# 01_Power.net
KiCad netlist of a schematic drawn in Altium Designer
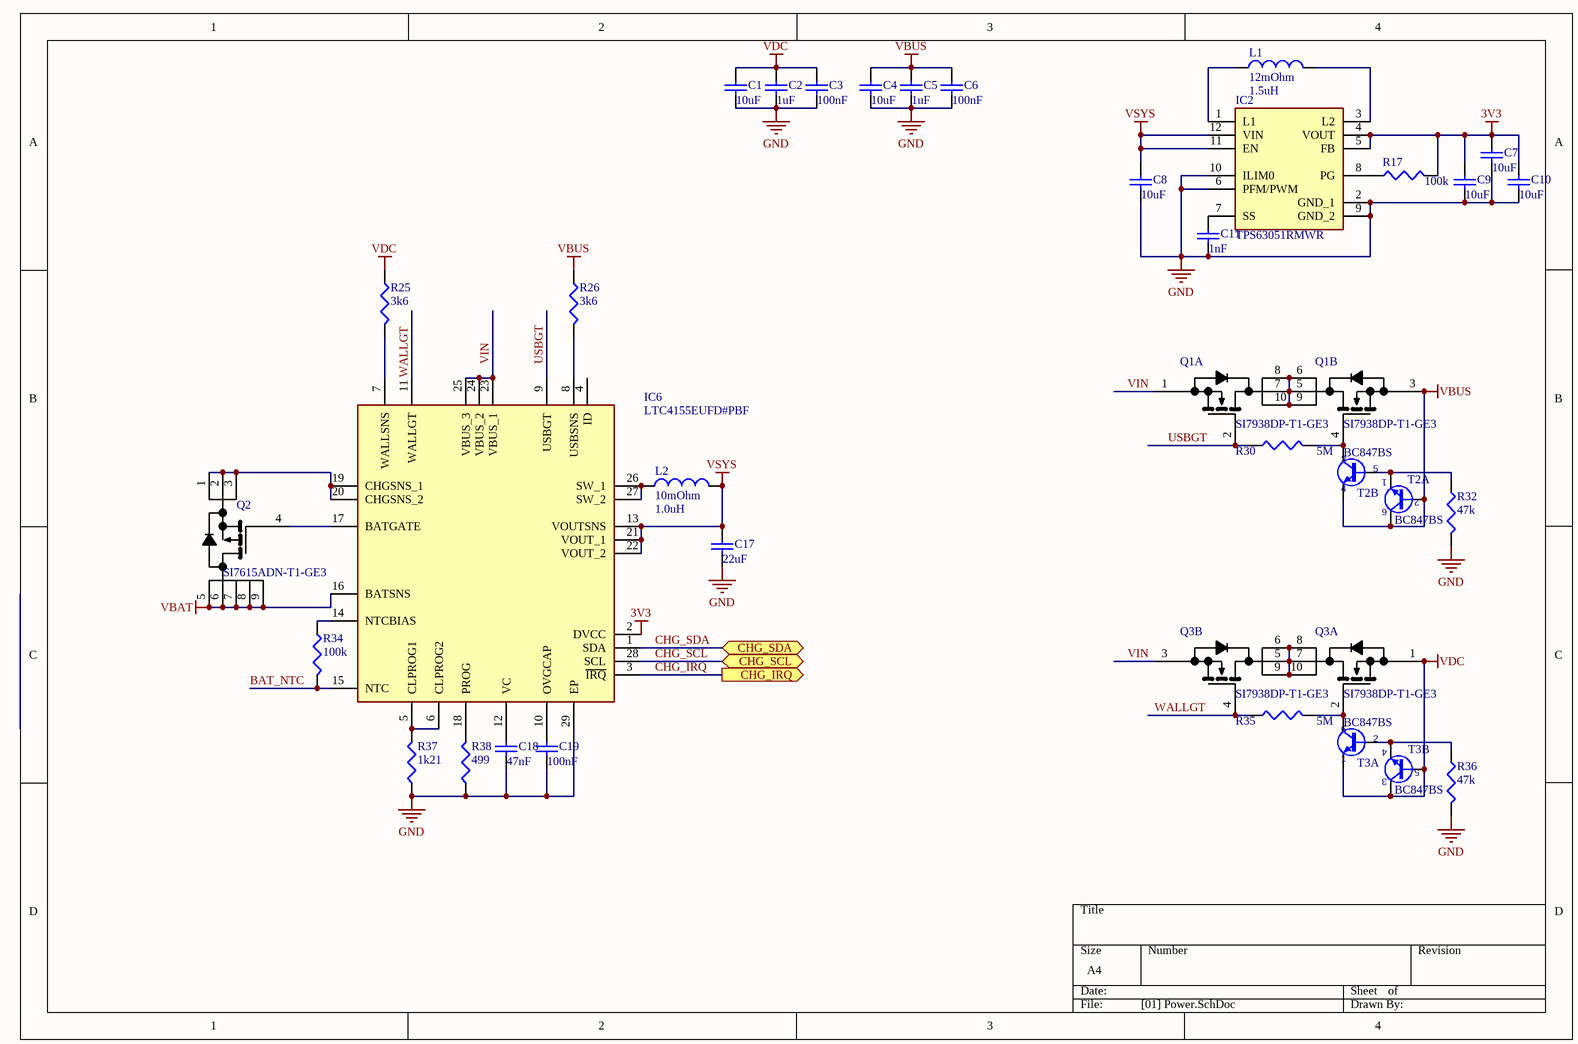
[diagram p0: [01] Power.SchDoc]

(export (version "E")
  (design (tool "Eeschema 10.0.6"))
  (components
    (comp (ref "C1")
      (value "10uF")
      (footprint "1608[0603]")
      (description "Capacitor (Semiconductor SIM Model)")
      (fields (field (name "Comment") "Cap Semi") (field (name "PUBLISHER") "Altium Limited"))
      (libsource (lib "Miscellaneous Devices") (part "Cap Semi"))
    )
    (comp (ref "C2")
      (value "1uF")
      (footprint "1608[0603]")
      (description "Capacitor (Semiconductor SIM Model)")
      (fields (field (name "Comment") "Cap Semi") (field (name "PUBLISHER") "Altium Limited"))
      (libsource (lib "Miscellaneous Devices") (part "Cap Semi"))
    )
    (comp (ref "C3")
      (value "100nF")
      (footprint "1608[0603]")
      (description "Capacitor (Semiconductor SIM Model)")
      (fields (field (name "Comment") "Cap Semi") (field (name "PUBLISHER") "Altium Limited"))
      (libsource (lib "Miscellaneous Devices") (part "Cap Semi"))
    )
    (comp (ref "C4")
      (value "10uF")
      (footprint "1608[0603]")
      (description "Capacitor (Semiconductor SIM Model)")
      (fields (field (name "Comment") "Cap Semi") (field (name "PUBLISHER") "Altium Limited"))
      (libsource (lib "Miscellaneous Devices") (part "Cap Semi"))
    )
    (comp (ref "C5")
      (value "1uF")
      (footprint "1608[0603]")
      (description "Capacitor (Semiconductor SIM Model)")
      (fields (field (name "Comment") "Cap Semi") (field (name "PUBLISHER") "Altium Limited"))
      (libsource (lib "Miscellaneous Devices") (part "Cap Semi"))
    )
    (comp (ref "C6")
      (value "100nF")
      (footprint "1608[0603]")
      (description "Capacitor (Semiconductor SIM Model)")
      (fields (field (name "Comment") "Cap Semi") (field (name "PUBLISHER") "Altium Limited"))
      (libsource (lib "Miscellaneous Devices") (part "Cap Semi"))
    )
    (comp (ref "C7")
      (value "10uF")
      (footprint "1608[0603]")
      (description "Capacitor (Semiconductor SIM Model)")
      (fields (field (name "Comment") "Cap Semi") (field (name "PUBLISHER") "Altium Limited"))
      (libsource (lib "Miscellaneous Devices") (part "Cap Semi"))
    )
    (comp (ref "C8")
      (value "10uF")
      (footprint "1608[0603]")
      (description "Capacitor (Semiconductor SIM Model)")
      (fields (field (name "Comment") "Cap Semi") (field (name "PUBLISHER") "Altium Limited"))
      (libsource (lib "Miscellaneous Devices") (part "Cap Semi"))
    )
    (comp (ref "C9")
      (value "10uF")
      (footprint "1608[0603]")
      (description "Capacitor (Semiconductor SIM Model)")
      (fields (field (name "Comment") "Cap Semi") (field (name "PUBLISHER") "Altium Limited"))
      (libsource (lib "Miscellaneous Devices") (part "Cap Semi"))
    )
    (comp (ref "C10")
      (value "10uF")
      (footprint "1608[0603]")
      (description "Capacitor (Semiconductor SIM Model)")
      (fields (field (name "Comment") "Cap Semi") (field (name "PUBLISHER") "Altium Limited"))
      (libsource (lib "Miscellaneous Devices") (part "Cap Semi"))
    )
    (comp (ref "C11")
      (value "1nF")
      (footprint "1608[0603]")
      (description "Capacitor (Semiconductor SIM Model)")
      (fields (field (name "Comment") "Cap Semi") (field (name "PUBLISHER") "Altium Limited"))
      (libsource (lib "Miscellaneous Devices") (part "Cap Semi"))
    )
    (comp (ref "C17")
      (value "22uF")
      (footprint "1608[0603]")
      (description "Capacitor (Semiconductor SIM Model)")
      (fields (field (name "Comment") "Cap Semi") (field (name "PUBLISHER") "Altium Limited"))
      (libsource (lib "Miscellaneous Devices") (part "Cap Semi"))
    )
    (comp (ref "C18")
      (value "47nF")
      (footprint "1608[0603]")
      (description "Capacitor (Semiconductor SIM Model)")
      (fields (field (name "Comment") "Cap Semi") (field (name "PUBLISHER") "Altium Limited"))
      (libsource (lib "Miscellaneous Devices") (part "Cap Semi"))
    )
    (comp (ref "C19")
      (value "100nF")
      (footprint "1608[0603]")
      (description "Capacitor (Semiconductor SIM Model)")
      (fields (field (name "Comment") "Cap Semi") (field (name "PUBLISHER") "Altium Limited"))
      (libsource (lib "Miscellaneous Devices") (part "Cap Semi"))
    )
    (comp (ref "IC2")
      (value "TPS63051RMWR")
      (footprint "SamacSys:QFN50P250X250X100-12N-D")
      (description "Integrated Circuit")
      (libsource (lib "SamacSys") (part "TPS63051RMWR"))
    )
    (comp (ref "IC6")
      (value "LTC4155EUFD#PBF")
      (footprint "SamacSys:QFN50P400X500X80-29N-D")
      (description "Integrated Circuit")
      (libsource (lib "SamacSys") (part "LTC4155EUFD#PBF"))
    )
    (comp (ref "L1")
      (value "12mOhm")
      (footprint "INDP2523X23N")
      (description "Inductor SRN6045TA-1R5Y")
      (fields (field (name "ALTIUM_VALUE") "1.5uH") (field (name "PUBLISHER") "Altium Limited"))
      (libsource (lib "Miscellaneous Devices") (part "Inductor"))
    )
    (comp (ref "L2")
      (value "10mOhm")
      (footprint "INDP2523X23N")
      (description "Inductor SRN6045TA-1R0Y")
      (fields (field (name "ALTIUM_VALUE") "1.0uH") (field (name "PUBLISHER") "Altium Limited"))
      (libsource (lib "Miscellaneous Devices") (part "Inductor"))
    )
    (comp (ref "Q1")
      (value "SI7938DP-T1-GE3")
      (footprint "SamacSys:POWERPAK-SO8_1")
      (description "MOSFET (N-Channel)")
      (libsource (lib "SamacSys") (part "SI7938DP-T1-GE3"))
    )
    (comp (ref "Q2")
      (value "SI7615ADN-T1-GE3")
      (footprint "SamacSys:PowerPAK1212-8 Single")
      (description "MOSFET (P-Channel)")
      (fields (field (name "MANUFACTURER_PART_NUMBER") "SIS413DN-T1-GE3"))
      (libsource (lib "SamacSys") (part "SI7615ADN-T1-GE3"))
    )
    (comp (ref "Q3")
      (value "SI7938DP-T1-GE3")
      (footprint "SamacSys:POWERPAK-SO8_1")
      (description "MOSFET (N-Channel)")
      (libsource (lib "SamacSys") (part "SI7938DP-T1-GE3"))
    )
    (comp (ref "R17")
      (value "100k")
      (footprint "J1-0603")
      (description "Resistor")
      (fields (field (name "Comment") "Res3") (field (name "PUBLISHER") "Altium Limited"))
      (libsource (lib "Miscellaneous Devices") (part "Res3"))
    )
    (comp (ref "R25")
      (value "3k6")
      (footprint "J1-0603")
      (description "Resistor")
      (fields (field (name "Comment") "Res3") (field (name "PUBLISHER") "Altium Limited"))
      (libsource (lib "Miscellaneous Devices") (part "Res3"))
    )
    (comp (ref "R26")
      (value "3k6")
      (footprint "J1-0603")
      (description "Resistor")
      (fields (field (name "Comment") "Res3") (field (name "PUBLISHER") "Altium Limited"))
      (libsource (lib "Miscellaneous Devices") (part "Res3"))
    )
    (comp (ref "R30")
      (value "5M")
      (footprint "J1-0603")
      (description "Resistor")
      (fields (field (name "Comment") "Res3") (field (name "PUBLISHER") "Altium Limited"))
      (libsource (lib "Miscellaneous Devices") (part "Res3"))
    )
    (comp (ref "R32")
      (value "47k")
      (footprint "J1-0603")
      (description "Resistor")
      (fields (field (name "Comment") "Res3") (field (name "PUBLISHER") "Altium Limited"))
      (libsource (lib "Miscellaneous Devices") (part "Res3"))
    )
    (comp (ref "R34")
      (value "100k")
      (footprint "J1-0603")
      (description "Resistor")
      (fields (field (name "Comment") "Res3") (field (name "PUBLISHER") "Altium Limited"))
      (libsource (lib "Miscellaneous Devices") (part "Res3"))
    )
    (comp (ref "R35")
      (value "5M")
      (footprint "J1-0603")
      (description "Resistor")
      (fields (field (name "Comment") "Res3") (field (name "PUBLISHER") "Altium Limited"))
      (libsource (lib "Miscellaneous Devices") (part "Res3"))
    )
    (comp (ref "R36")
      (value "47k")
      (footprint "J1-0603")
      (description "Resistor")
      (fields (field (name "Comment") "Res3") (field (name "PUBLISHER") "Altium Limited"))
      (libsource (lib "Miscellaneous Devices") (part "Res3"))
    )
    (comp (ref "R37")
      (value "1k21")
      (footprint "J1-0603")
      (description "Resistor")
      (fields (field (name "Comment") "Res3") (field (name "PUBLISHER") "Altium Limited"))
      (libsource (lib "Miscellaneous Devices") (part "Res3"))
    )
    (comp (ref "R38")
      (value "499")
      (footprint "J1-0603")
      (description "Resistor")
      (fields (field (name "Comment") "Res3") (field (name "PUBLISHER") "Altium Limited"))
      (libsource (lib "Miscellaneous Devices") (part "Res3"))
    )
    (comp (ref "T2")
      (value "BC847BS")
      (footprint "SOT65P210X110-6N")
      (description "45V 100mA Dual NPN General-Purpose Transistor")
      (fields (field (name "MANUFACTURER") "NXP SEMICONDUCTORS") (field (name "AUTHOR") "CERN DEM JMW"))
      (libsource (lib "") (part "BC847BS_1"))
    )
    (comp (ref "T3")
      (value "BC847BS")
      (footprint "SOT65P210X110-6N")
      (description "45V 100mA Dual NPN General-Purpose Transistor")
      (fields (field (name "MANUFACTURER") "NXP SEMICONDUCTORS") (field (name "AUTHOR") "CERN DEM JMW"))
      (libsource (lib "ICs And Semiconductors") (part "BC847BS"))
    )
  )
  (nets
    (net (code "1") (name "/BAT_NTC") (class "Default")
      (node (ref "IC6") (pin "15") (pinfunction "NTC_15") (pintype "passive"))
      (node (ref "R34") (pin "2") (pinfunction "2_2") (pintype "passive"))
    )
    (net (code "2") (name "/CHG_IRQ") (class "Default")
      (node (ref "IC6") (pin "3") (pinfunction "~{IRQ}_3") (pintype "passive"))
    )
    (net (code "3") (name "/CHG_SCL") (class "Default")
      (node (ref "IC6") (pin "28") (pinfunction "SCL_28") (pintype "passive"))
    )
    (net (code "4") (name "/CHG_SDA") (class "Default")
      (node (ref "IC6") (pin "1") (pinfunction "SDA_1") (pintype "passive"))
    )
    (net (code "5") (name "/USBGT") (class "Default")
      (node (ref "IC6") (pin "9") (pinfunction "USBGT_9") (pintype "passive"))
      (node (ref "Q1") (pin "2") (pinfunction "G1_2") (pintype "passive"))
      (node (ref "R30") (pin "1") (pinfunction "1_1") (pintype "passive"))
    )
    (net (code "6") (name "/VIN") (class "Default")
      (node (ref "IC6") (pin "23") (pinfunction "VBUS_1_23") (pintype "passive"))
      (node (ref "IC6") (pin "24") (pinfunction "VBUS_2_24") (pintype "passive"))
      (node (ref "IC6") (pin "25") (pinfunction "VBUS_3_25") (pintype "passive"))
      (node (ref "Q1") (pin "1") (pinfunction "S1_1") (pintype "passive"))
      (node (ref "Q3") (pin "3") (pinfunction "S2_3") (pintype "passive"))
    )
    (net (code "7") (name "/WALLGT") (class "Default")
      (node (ref "IC6") (pin "11") (pinfunction "WALLGT_11") (pintype "passive"))
      (node (ref "Q3") (pin "4") (pinfunction "G2_4") (pintype "passive"))
      (node (ref "R35") (pin "1") (pinfunction "1_1") (pintype "passive"))
    )
    (net (code "8") (name "3V3") (class "Default")
      (node (ref "C10") (pin "2") (pinfunction "2_2") (pintype "passive"))
      (node (ref "C7") (pin "2") (pinfunction "2_2") (pintype "passive"))
      (node (ref "C9") (pin "2") (pinfunction "2_2") (pintype "passive"))
      (node (ref "IC2") (pin "4") (pinfunction "VOUT_4") (pintype "passive"))
      (node (ref "IC2") (pin "5") (pinfunction "FB_5") (pintype "passive"))
      (node (ref "IC6") (pin "2") (pinfunction "DVCC_2") (pintype "passive"))
      (node (ref "R17") (pin "2") (pinfunction "2_2") (pintype "passive"))
    )
    (net (code "9") (name "GND") (class "Default")
      (node (ref "C1") (pin "1") (pinfunction "1_1") (pintype "passive"))
      (node (ref "C10") (pin "1") (pinfunction "1_1") (pintype "passive"))
      (node (ref "C11") (pin "1") (pinfunction "1_1") (pintype "passive"))
      (node (ref "C17") (pin "1") (pinfunction "1_1") (pintype "passive"))
      (node (ref "C18") (pin "1") (pinfunction "1_1") (pintype "passive"))
      (node (ref "C19") (pin "1") (pinfunction "1_1") (pintype "passive"))
      (node (ref "C2") (pin "1") (pinfunction "1_1") (pintype "passive"))
      (node (ref "C3") (pin "1") (pinfunction "1_1") (pintype "passive"))
      (node (ref "C4") (pin "1") (pinfunction "1_1") (pintype "passive"))
      (node (ref "C5") (pin "1") (pinfunction "1_1") (pintype "passive"))
      (node (ref "C6") (pin "1") (pinfunction "1_1") (pintype "passive"))
      (node (ref "C7") (pin "1") (pinfunction "1_1") (pintype "passive"))
      (node (ref "C8") (pin "1") (pinfunction "1_1") (pintype "passive"))
      (node (ref "C9") (pin "1") (pinfunction "1_1") (pintype "passive"))
      (node (ref "IC2") (pin "10") (pinfunction "ILIM0_10") (pintype "passive"))
      (node (ref "IC2") (pin "2") (pinfunction "GND_1_2") (pintype "passive"))
      (node (ref "IC2") (pin "6") (pinfunction "PFM/PWM_6") (pintype "passive"))
      (node (ref "IC2") (pin "9") (pinfunction "GND_2_9") (pintype "passive"))
      (node (ref "IC6") (pin "29") (pinfunction "EP_29") (pintype "passive"))
      (node (ref "R32") (pin "2") (pinfunction "2_2") (pintype "passive"))
      (node (ref "R36") (pin "2") (pinfunction "2_2") (pintype "passive"))
      (node (ref "R37") (pin "1") (pinfunction "1_1") (pintype "passive"))
      (node (ref "R38") (pin "1") (pinfunction "1_1") (pintype "passive"))
    )
    (net (code "10") (name "Net-(IC2-L1)") (class "Default")
      (node (ref "IC2") (pin "1") (pinfunction "L1_1") (pintype "passive"))
      (node (ref "L1") (pin "1") (pinfunction "1_1") (pintype "passive"))
    )
    (net (code "11") (name "Net-(IC2-L2)") (class "Default")
      (node (ref "IC2") (pin "3") (pinfunction "L2_3") (pintype "passive"))
      (node (ref "L1") (pin "2") (pinfunction "2_2") (pintype "passive"))
    )
    (net (code "12") (name "Net-(IC2-PG)") (class "Default")
      (node (ref "IC2") (pin "8") (pinfunction "PG_8") (pintype "passive"))
      (node (ref "R17") (pin "1") (pinfunction "1_1") (pintype "passive"))
    )
    (net (code "13") (name "Net-(IC2-SS)") (class "Default")
      (node (ref "C11") (pin "2") (pinfunction "2_2") (pintype "passive"))
      (node (ref "IC2") (pin "7") (pinfunction "SS_7") (pintype "passive"))
    )
    (net (code "14") (name "Net-(IC6-BATGATE)") (class "Default")
      (node (ref "IC6") (pin "17") (pinfunction "BATGATE_17") (pintype "passive"))
      (node (ref "Q2") (pin "4") (pinfunction "G_4") (pintype "passive"))
    )
    (net (code "15") (name "Net-(IC6-CHGSNS_1)") (class "Default")
      (node (ref "IC6") (pin "19") (pinfunction "CHGSNS_1_19") (pintype "passive"))
      (node (ref "IC6") (pin "20") (pinfunction "CHGSNS_2_20") (pintype "passive"))
      (node (ref "Q2") (pin "1") (pinfunction "S_1") (pintype "passive"))
      (node (ref "Q2") (pin "2") (pinfunction "S_2") (pintype "passive"))
      (node (ref "Q2") (pin "3") (pinfunction "S_3") (pintype "passive"))
    )
    (net (code "16") (name "Net-(IC6-CLPROG1)") (class "Default")
      (node (ref "IC6") (pin "5") (pinfunction "CLPROG1_5") (pintype "passive"))
      (node (ref "IC6") (pin "6") (pinfunction "CLPROG2_6") (pintype "passive"))
      (node (ref "R37") (pin "2") (pinfunction "2_2") (pintype "passive"))
    )
    (net (code "17") (name "Net-(IC6-NTCBIAS)") (class "Default")
      (node (ref "IC6") (pin "14") (pinfunction "NTCBIAS_14") (pintype "passive"))
      (node (ref "R34") (pin "1") (pinfunction "1_1") (pintype "passive"))
    )
    (net (code "18") (name "Net-(IC6-OVGCAP)") (class "Default")
      (node (ref "C19") (pin "2") (pinfunction "2_2") (pintype "passive"))
      (node (ref "IC6") (pin "10") (pinfunction "OVGCAP_10") (pintype "passive"))
    )
    (net (code "19") (name "Net-(IC6-PROG)") (class "Default")
      (node (ref "IC6") (pin "18") (pinfunction "PROG_18") (pintype "passive"))
      (node (ref "R38") (pin "2") (pinfunction "2_2") (pintype "passive"))
    )
    (net (code "20") (name "Net-(IC6-SW_1)") (class "Default")
      (node (ref "IC6") (pin "26") (pinfunction "SW_1_26") (pintype "passive"))
      (node (ref "IC6") (pin "27") (pinfunction "SW_2_27") (pintype "passive"))
      (node (ref "L2") (pin "1") (pinfunction "1_1") (pintype "passive"))
    )
    (net (code "21") (name "Net-(IC6-USBSNS)") (class "Default")
      (node (ref "IC6") (pin "8") (pinfunction "USBSNS_8") (pintype "passive"))
      (node (ref "R26") (pin "2") (pinfunction "2_2") (pintype "passive"))
    )
    (net (code "22") (name "Net-(IC6-VC)") (class "Default")
      (node (ref "C18") (pin "2") (pinfunction "2_2") (pintype "passive"))
      (node (ref "IC6") (pin "12") (pinfunction "VC_12") (pintype "passive"))
    )
    (net (code "23") (name "Net-(IC6-WALLSNS)") (class "Default")
      (node (ref "IC6") (pin "7") (pinfunction "WALLSNS_7") (pintype "passive"))
      (node (ref "R25") (pin "2") (pinfunction "2_2") (pintype "passive"))
    )
    (net (code "24") (name "Net-(Q1A-D1_1)") (class "Default")
      (node (ref "Q1") (pin "10") (pinfunction "D1_3_10") (pintype "passive"))
      (node (ref "Q1") (pin "5") (pinfunction "D2_1_5") (pintype "passive"))
      (node (ref "Q1") (pin "6") (pinfunction "D2_2_6") (pintype "passive"))
      (node (ref "Q1") (pin "7") (pinfunction "D1_1_7") (pintype "passive"))
      (node (ref "Q1") (pin "8") (pinfunction "D1_2_8") (pintype "passive"))
      (node (ref "Q1") (pin "9") (pinfunction "D2_3_9") (pintype "passive"))
    )
    (net (code "25") (name "Net-(Q1B-G2)") (class "Default")
      (node (ref "Q1") (pin "4") (pinfunction "G2_4") (pintype "passive"))
      (node (ref "R30") (pin "2") (pinfunction "2_2") (pintype "passive"))
      (node (ref "T2") (pin "3") (pinfunction "C_3") (pintype "passive"))
    )
    (net (code "26") (name "Net-(Q3A-D1_1)") (class "Default")
      (node (ref "Q3") (pin "10") (pinfunction "D1_3_10") (pintype "passive"))
      (node (ref "Q3") (pin "5") (pinfunction "D2_1_5") (pintype "passive"))
      (node (ref "Q3") (pin "6") (pinfunction "D2_2_6") (pintype "passive"))
      (node (ref "Q3") (pin "7") (pinfunction "D1_1_7") (pintype "passive"))
      (node (ref "Q3") (pin "8") (pinfunction "D1_2_8") (pintype "passive"))
      (node (ref "Q3") (pin "9") (pinfunction "D2_3_9") (pintype "passive"))
    )
    (net (code "27") (name "Net-(Q3A-G1)") (class "Default")
      (node (ref "Q3") (pin "2") (pinfunction "G1_2") (pintype "passive"))
      (node (ref "R35") (pin "2") (pinfunction "2_2") (pintype "passive"))
      (node (ref "T3") (pin "6") (pinfunction "C_6") (pintype "passive"))
    )
    (net (code "28") (name "Net-(T2A-E)") (class "Default")
      (node (ref "R32") (pin "1") (pinfunction "1_1") (pintype "passive"))
      (node (ref "T2") (pin "1") (pinfunction "E_1") (pintype "passive"))
      (node (ref "T2") (pin "5") (pinfunction "B_5") (pintype "passive"))
    )
    (net (code "29") (name "Net-(T3A-B)") (class "Default")
      (node (ref "R36") (pin "1") (pinfunction "1_1") (pintype "passive"))
      (node (ref "T3") (pin "2") (pinfunction "B_2") (pintype "passive"))
      (node (ref "T3") (pin "4") (pinfunction "E_4") (pintype "passive"))
    )
    (net (code "30") (name "VBAT") (class "Default")
      (node (ref "IC6") (pin "16") (pinfunction "BATSNS_16") (pintype "passive"))
      (node (ref "Q2") (pin "5") (pinfunction "D_5") (pintype "passive"))
      (node (ref "Q2") (pin "6") (pinfunction "D_6") (pintype "passive"))
      (node (ref "Q2") (pin "7") (pinfunction "D_7") (pintype "passive"))
      (node (ref "Q2") (pin "8") (pinfunction "D_8") (pintype "passive"))
      (node (ref "Q2") (pin "9") (pinfunction "D_9") (pintype "passive"))
    )
    (net (code "31") (name "VBUS") (class "Default")
      (node (ref "C4") (pin "2") (pinfunction "2_2") (pintype "passive"))
      (node (ref "C5") (pin "2") (pinfunction "2_2") (pintype "passive"))
      (node (ref "C6") (pin "2") (pinfunction "2_2") (pintype "passive"))
      (node (ref "Q1") (pin "3") (pinfunction "S2_3") (pintype "passive"))
      (node (ref "R26") (pin "1") (pinfunction "1_1") (pintype "passive"))
      (node (ref "T2") (pin "2") (pinfunction "B_2") (pintype "passive"))
      (node (ref "T2") (pin "4") (pinfunction "E_4") (pintype "passive"))
      (node (ref "T2") (pin "6") (pinfunction "C_6") (pintype "passive"))
    )
    (net (code "32") (name "VDC") (class "Default")
      (node (ref "C1") (pin "2") (pinfunction "2_2") (pintype "passive"))
      (node (ref "C2") (pin "2") (pinfunction "2_2") (pintype "passive"))
      (node (ref "C3") (pin "2") (pinfunction "2_2") (pintype "passive"))
      (node (ref "Q3") (pin "1") (pinfunction "S1_1") (pintype "passive"))
      (node (ref "R25") (pin "1") (pinfunction "1_1") (pintype "passive"))
      (node (ref "T3") (pin "1") (pinfunction "E_1") (pintype "passive"))
      (node (ref "T3") (pin "3") (pinfunction "C_3") (pintype "passive"))
      (node (ref "T3") (pin "5") (pinfunction "B_5") (pintype "passive"))
    )
    (net (code "33") (name "VSYS") (class "Default")
      (node (ref "C17") (pin "2") (pinfunction "2_2") (pintype "passive"))
      (node (ref "C8") (pin "2") (pinfunction "2_2") (pintype "passive"))
      (node (ref "IC2") (pin "11") (pinfunction "EN_11") (pintype "passive"))
      (node (ref "IC2") (pin "12") (pinfunction "VIN_12") (pintype "passive"))
      (node (ref "IC6") (pin "13") (pinfunction "VOUTSNS_13") (pintype "passive"))
      (node (ref "IC6") (pin "21") (pinfunction "VOUT_1_21") (pintype "passive"))
      (node (ref "IC6") (pin "22") (pinfunction "VOUT_2_22") (pintype "passive"))
      (node (ref "L2") (pin "2") (pinfunction "2_2") (pintype "passive"))
    )
    (net (code "34") (name "unconnected-(IC6-ID-Pad4)") (class "Default")
      (node (ref "IC6") (pin "4") (pinfunction "ID_4") (pintype "passive"))
    )
  )
)
